# MIDI_Interface.net
KiCad netlist of a schematic drawn in Altium Designer
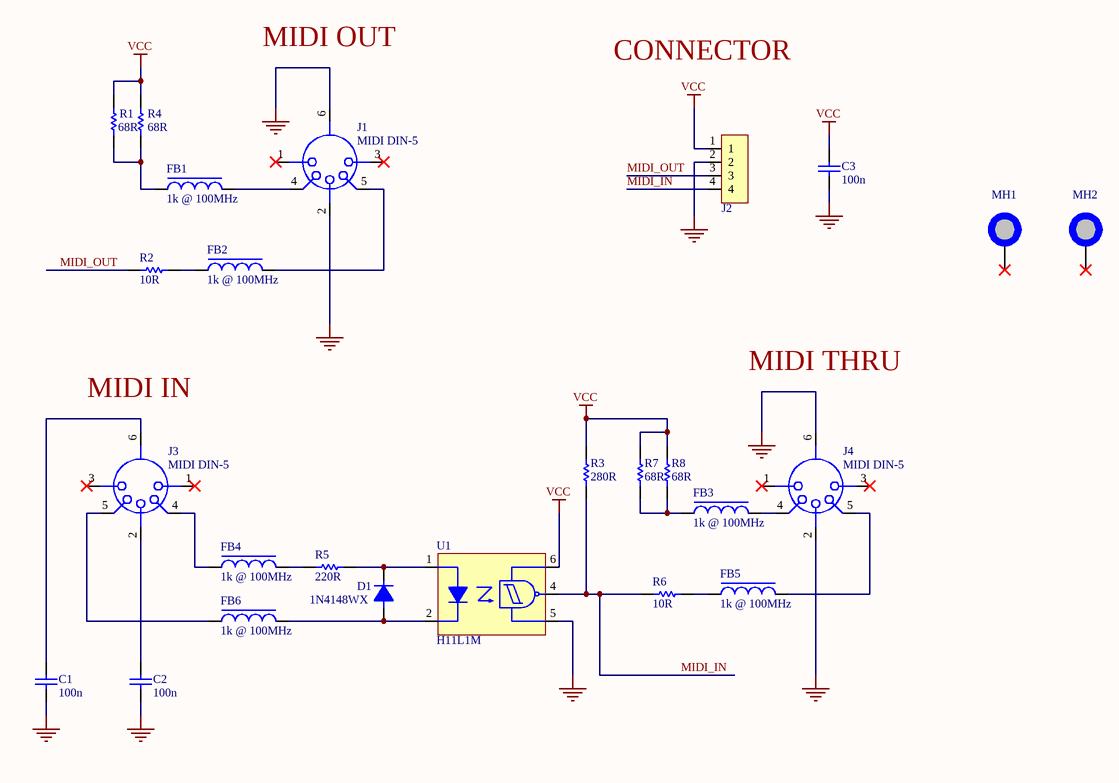
[diagram p0: MIDI_Interface.SchDoc]

(export (version "E")
  (design (tool "Eeschema 10.0.6"))
  (components
    (comp (ref "C1")
      (value "100n")
      (footprint "C0603")
      (libsource (lib "UserLibrary") (part "C0603KC0G100V104"))
    )
    (comp (ref "C2")
      (value "100n")
      (footprint "C0603")
      (libsource (lib "UserLibrary") (part "C0603KC0G100V104"))
    )
    (comp (ref "C3")
      (value "100n")
      (footprint "C0603")
      (libsource (lib "UserLibrary") (part "C0603KC0G100V104"))
    )
    (comp (ref "D1")
      (value "1N4148WX")
      (footprint "SOD323")
      (libsource (lib "UserLibrary") (part "1N4148WX"))
    )
    (comp (ref "FB1")
      (value "1k @ 100MHz")
      (footprint "FB0603")
      (libsource (lib "UserLibrary") (part "FB0603"))
    )
    (comp (ref "FB2")
      (value "1k @ 100MHz")
      (footprint "FB0603")
      (libsource (lib "UserLibrary") (part "FB0603"))
    )
    (comp (ref "FB3")
      (value "1k @ 100MHz")
      (footprint "FB0603")
      (libsource (lib "UserLibrary") (part "FB0603"))
    )
    (comp (ref "FB4")
      (value "1k @ 100MHz")
      (footprint "FB0603")
      (libsource (lib "UserLibrary") (part "FB0603"))
    )
    (comp (ref "FB5")
      (value "1k @ 100MHz")
      (footprint "FB0603")
      (libsource (lib "UserLibrary") (part "FB0603"))
    )
    (comp (ref "FB6")
      (value "1k @ 100MHz")
      (footprint "FB0603")
      (libsource (lib "UserLibrary") (part "FB0603"))
    )
    (comp (ref "J1")
      (value "MIDI DIN-5")
      (footprint "5 PIN MIDI")
      (libsource (lib "UserLibrary") (part "MIDI DIN"))
    )
    (comp (ref "J2")
      (value "HDR 1x4")
      (footprint "HDR M 1x4 2.54MM")
      (libsource (lib "UserLibrary") (part "HDR M 1x4 2.54MM"))
    )
    (comp (ref "J3") (value "MIDI DIN-5") (footprint "5 PIN MIDI") (libsource (lib "") (part "MIDI DIN_1")))
    (comp (ref "J4")
      (value "MIDI DIN-5")
      (footprint "5 PIN MIDI")
      (libsource (lib "UserLibrary") (part "MIDI DIN"))
    )
    (comp (ref "MH1")
      (value "MH_7.4MMNC_3.2MMD")
      (footprint "MH_7.4MMD_3.2MMD_NON_COPPER_NPTH")
      (description "Mounting Hole 7.4mm Diameter (Non Copper), 3.2 Drill NPTH")
      (libsource (lib "UserLibrary") (part "MH_7.4MMNC_3.2MMD"))
    )
    (comp (ref "MH2")
      (value "MH_7.4MMNC_3.2MMD")
      (footprint "MH_7.4MMD_3.2MMD_NON_COPPER_NPTH")
      (description "Mounting Hole 7.4mm Diameter (Non Copper), 3.2 Drill NPTH")
      (libsource (lib "UserLibrary") (part "MH_7.4MMNC_3.2MMD"))
    )
    (comp (ref "R1") (value "68R") (footprint "R0805") (libsource (lib "UserLibrary") (part "R0805F68R")))
    (comp (ref "R2") (value "10R") (footprint "R0805") (libsource (lib "UserLibrary") (part "R0805F10R")))
    (comp (ref "R3") (value "280R") (footprint "R0805") (libsource (lib "UserLibrary") (part "R0805F280R")))
    (comp (ref "R4") (value "68R") (footprint "R0805") (libsource (lib "UserLibrary") (part "R0805F68R")))
    (comp (ref "R5") (value "220R") (footprint "R0805") (libsource (lib "UserLibrary") (part "R0805F220R")))
    (comp (ref "R6") (value "10R") (footprint "R0805") (libsource (lib "UserLibrary") (part "R0805F10R")))
    (comp (ref "R7") (value "68R") (footprint "R0805") (libsource (lib "UserLibrary") (part "R0805F68R")))
    (comp (ref "R8") (value "68R") (footprint "R0805") (libsource (lib "UserLibrary") (part "R0805F68R")))
    (comp (ref "U1") (value "H11L1M") (footprint "H11L1M") (libsource (lib "UserLibrary") (part "H11L1M")))
  )
  (nets
    (net (code "1") (name "/MIDI_IN") (class "Default")
      (node (ref "J2") (pin "4") (pinfunction "4_4") (pintype "passive"))
      (node (ref "R3") (pin "1") (pinfunction "1_1") (pintype "passive"))
      (node (ref "R6") (pin "1") (pinfunction "1_1") (pintype "passive"))
      (node (ref "U1") (pin "4") (pinfunction "Vo_4") (pintype "passive"))
    )
    (net (code "2") (name "/MIDI_OUT") (class "Default")
      (node (ref "J2") (pin "3") (pinfunction "3_3") (pintype "passive"))
      (node (ref "R2") (pin "1") (pinfunction "1_1") (pintype "passive"))
    )
    (net (code "3") (name "GND") (class "Default")
      (node (ref "C1") (pin "1") (pinfunction "1_1") (pintype "passive"))
      (node (ref "C2") (pin "1") (pinfunction "1_1") (pintype "passive"))
      (node (ref "C3") (pin "1") (pinfunction "1_1") (pintype "passive"))
      (node (ref "J1") (pin "2") (pinfunction "2_2") (pintype "passive"))
      (node (ref "J1") (pin "6") (pinfunction "6_6") (pintype "passive"))
      (node (ref "J2") (pin "2") (pinfunction "2_2") (pintype "passive"))
      (node (ref "J4") (pin "2") (pinfunction "2_2") (pintype "passive"))
      (node (ref "J4") (pin "6") (pinfunction "6_6") (pintype "passive"))
      (node (ref "U1") (pin "5") (pinfunction "GND_5") (pintype "passive"))
    )
    (net (code "4") (name "Net-(C1-Pad2)") (class "Default")
      (node (ref "C1") (pin "2") (pinfunction "2_2") (pintype "passive"))
      (node (ref "J3") (pin "6") (pinfunction "6_6") (pintype "passive"))
    )
    (net (code "5") (name "Net-(C2-Pad2)") (class "Default")
      (node (ref "C2") (pin "2") (pinfunction "2_2") (pintype "passive"))
      (node (ref "J3") (pin "2") (pinfunction "2_2") (pintype "passive"))
    )
    (net (code "6") (name "Net-(FB1-Pad1)") (class "Default")
      (node (ref "FB1") (pin "1") (pinfunction "1_1") (pintype "passive"))
      (node (ref "R1") (pin "1") (pinfunction "1_1") (pintype "passive"))
      (node (ref "R4") (pin "1") (pinfunction "1_1") (pintype "passive"))
    )
    (net (code "7") (name "Net-(FB1-Pad2)") (class "Default")
      (node (ref "FB1") (pin "2") (pinfunction "2_2") (pintype "passive"))
      (node (ref "J1") (pin "4") (pinfunction "4_4") (pintype "passive"))
    )
    (net (code "8") (name "Net-(FB2-Pad1)") (class "Default")
      (node (ref "FB2") (pin "1") (pinfunction "1_1") (pintype "passive"))
      (node (ref "R2") (pin "2") (pinfunction "2_2") (pintype "passive"))
    )
    (net (code "9") (name "Net-(FB2-Pad2)") (class "Default")
      (node (ref "FB2") (pin "2") (pinfunction "2_2") (pintype "passive"))
      (node (ref "J1") (pin "5") (pinfunction "5_5") (pintype "passive"))
    )
    (net (code "10") (name "Net-(FB3-Pad1)") (class "Default")
      (node (ref "FB3") (pin "1") (pinfunction "1_1") (pintype "passive"))
      (node (ref "R7") (pin "1") (pinfunction "1_1") (pintype "passive"))
      (node (ref "R8") (pin "1") (pinfunction "1_1") (pintype "passive"))
    )
    (net (code "11") (name "Net-(FB3-Pad2)") (class "Default")
      (node (ref "FB3") (pin "2") (pinfunction "2_2") (pintype "passive"))
      (node (ref "J4") (pin "4") (pinfunction "4_4") (pintype "passive"))
    )
    (net (code "12") (name "Net-(FB4-Pad1)") (class "Default")
      (node (ref "FB4") (pin "1") (pinfunction "1_1") (pintype "passive"))
      (node (ref "J3") (pin "4") (pinfunction "4_4") (pintype "passive"))
    )
    (net (code "13") (name "Net-(FB4-Pad2)") (class "Default")
      (node (ref "FB4") (pin "2") (pinfunction "2_2") (pintype "passive"))
      (node (ref "R5") (pin "1") (pinfunction "1_1") (pintype "passive"))
    )
    (net (code "14") (name "Net-(FB5-Pad1)") (class "Default")
      (node (ref "FB5") (pin "1") (pinfunction "1_1") (pintype "passive"))
      (node (ref "R6") (pin "2") (pinfunction "2_2") (pintype "passive"))
    )
    (net (code "15") (name "Net-(FB5-Pad2)") (class "Default")
      (node (ref "FB5") (pin "2") (pinfunction "2_2") (pintype "passive"))
      (node (ref "J4") (pin "5") (pinfunction "5_5") (pintype "passive"))
    )
    (net (code "16") (name "Net-(FB6-Pad1)") (class "Default")
      (node (ref "FB6") (pin "1") (pinfunction "1_1") (pintype "passive"))
      (node (ref "J3") (pin "5") (pinfunction "5_5") (pintype "passive"))
    )
    (net (code "17") (name "Net-(U1-A)") (class "Default")
      (node (ref "D1") (pin "2") (pinfunction "2_2") (pintype "passive"))
      (node (ref "R5") (pin "2") (pinfunction "2_2") (pintype "passive"))
      (node (ref "U1") (pin "1") (pinfunction "A_1") (pintype "passive"))
    )
    (net (code "18") (name "Net-(U1-K)") (class "Default")
      (node (ref "D1") (pin "1") (pinfunction "1_1") (pintype "passive"))
      (node (ref "FB6") (pin "2") (pinfunction "2_2") (pintype "passive"))
      (node (ref "U1") (pin "2") (pinfunction "K_2") (pintype "passive"))
    )
    (net (code "19") (name "VCC") (class "Default")
      (node (ref "C3") (pin "2") (pinfunction "2_2") (pintype "passive"))
      (node (ref "J2") (pin "1") (pinfunction "1_1") (pintype "passive"))
      (node (ref "R1") (pin "2") (pinfunction "2_2") (pintype "passive"))
      (node (ref "R3") (pin "2") (pinfunction "2_2") (pintype "passive"))
      (node (ref "R4") (pin "2") (pinfunction "2_2") (pintype "passive"))
      (node (ref "R7") (pin "2") (pinfunction "2_2") (pintype "passive"))
      (node (ref "R8") (pin "2") (pinfunction "2_2") (pintype "passive"))
      (node (ref "U1") (pin "6") (pinfunction "VCC_6") (pintype "passive"))
    )
    (net (code "20") (name "unconnected-(J1-Pad1)") (class "Default")
      (node (ref "J1") (pin "1") (pinfunction "1_1") (pintype "passive+no_connect"))
    )
    (net (code "21") (name "unconnected-(J1-Pad3)") (class "Default")
      (node (ref "J1") (pin "3") (pinfunction "3_3") (pintype "passive+no_connect"))
    )
    (net (code "22") (name "unconnected-(J3-Pad1)") (class "Default")
      (node (ref "J3") (pin "1") (pinfunction "1_1") (pintype "passive+no_connect"))
    )
    (net (code "23") (name "unconnected-(J3-Pad3)") (class "Default")
      (node (ref "J3") (pin "3") (pinfunction "3_3") (pintype "passive+no_connect"))
    )
    (net (code "24") (name "unconnected-(J4-Pad1)") (class "Default")
      (node (ref "J4") (pin "1") (pinfunction "1_1") (pintype "passive+no_connect"))
    )
    (net (code "25") (name "unconnected-(J4-Pad3)") (class "Default")
      (node (ref "J4") (pin "3") (pinfunction "3_3") (pintype "passive+no_connect"))
    )
    (net (code "26") (name "unconnected-(MH1-Pad1)") (class "Default")
      (node (ref "MH1") (pin "1") (pinfunction "1_1") (pintype "passive+no_connect"))
    )
    (net (code "27") (name "unconnected-(MH2-Pad1)") (class "Default")
      (node (ref "MH2") (pin "1") (pinfunction "1_1") (pintype "passive+no_connect"))
    )
  )
)
